# ESP_Robo_Board.net
KiCad netlist of a schematic drawn in EAGLE
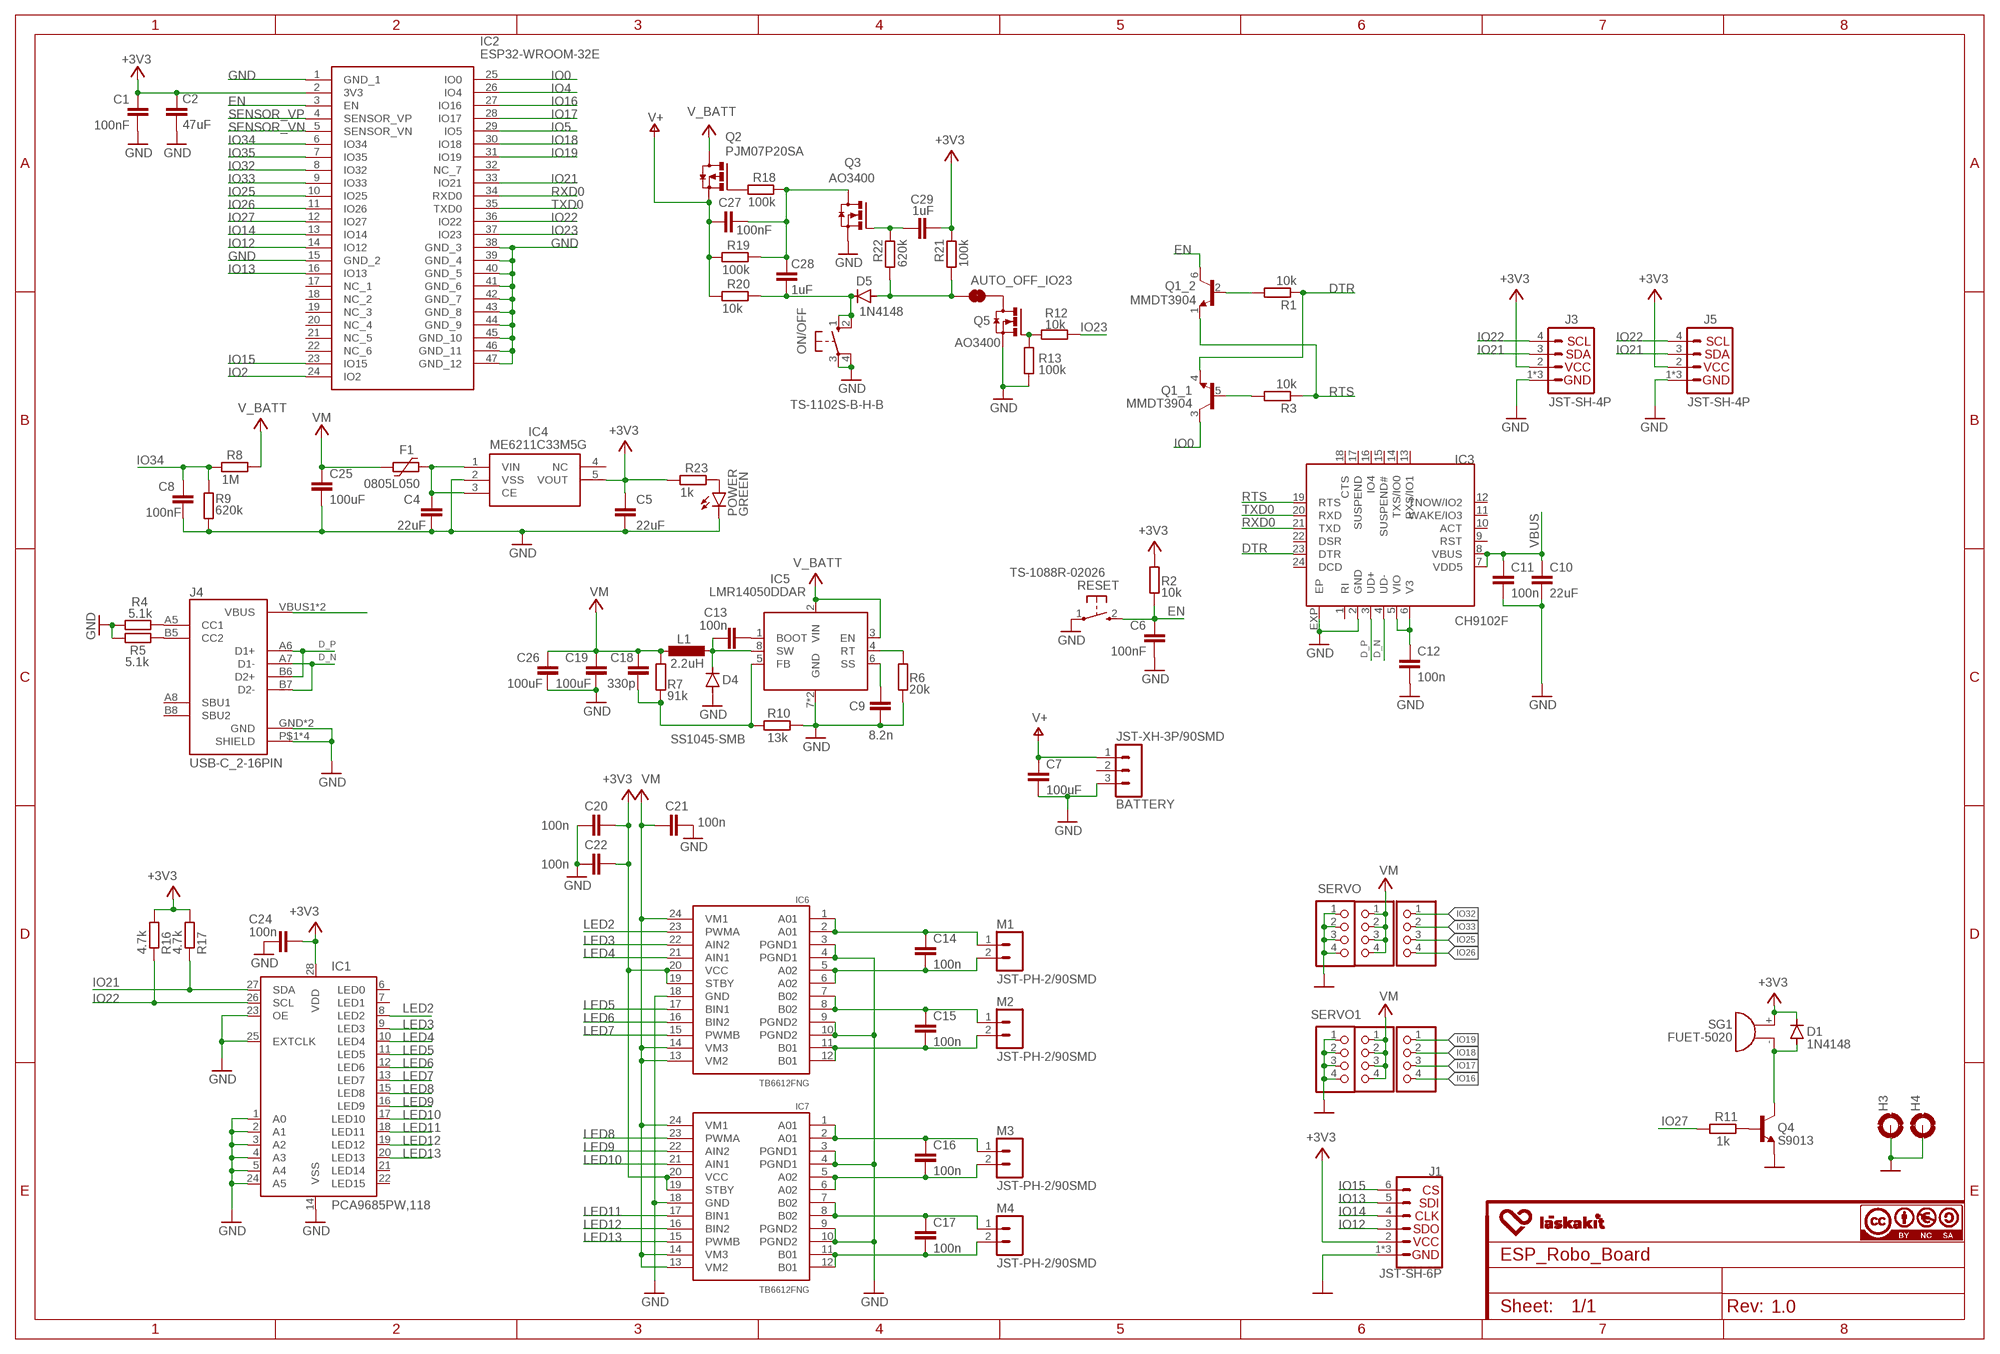
[diagram p0: schematic, sheet 1]

(export (version "E")
  (design (tool "Eeschema 10.0.6"))
  (components
    (comp (ref "1")
      (value "PINHD_1X4_RED")
      (footprint "eagle-import:1X04")
      (libsource (lib "eagle-import") (part "PINHD-1X4"))
    )
    (comp (ref "2")
      (value "PINHD_1X4_BLACK")
      (footprint "eagle-import:1X04")
      (libsource (lib "eagle-import") (part "PINHD-1X4"))
    )
    (comp (ref "5")
      (value "PINHD_1X4_RED")
      (footprint "eagle-import:1X04")
      (libsource (lib "eagle-import") (part "PINHD-1X4"))
    )
    (comp (ref "6")
      (value "PINHD_1X4_BLACK")
      (footprint "eagle-import:1X04")
      (libsource (lib "eagle-import") (part "PINHD-1X4"))
    )
    (comp (ref "AUTO_OFF_IO23")
      (value "nv")
      (footprint "eagle-import:SMT-JUMPER_2_NC_TRACE_SILK")
      (libsource (lib "eagle-import") (part "JUMPER-SMT_2_NC_TRACE_SILK"))
    )
    (comp (ref "BATTERY")
      (value "JST-XH-3P/90SMD")
      (footprint "eagle-import:S3B-XH-SM4")
      (libsource (lib "eagle-import") (part "JST-XH-3/90SMD"))
    )
    (comp (ref "C1")
      (value "100nF")
      (footprint "eagle-import:C0603")
      (libsource (lib "eagle-import") (part "C-EUC0603"))
    )
    (comp (ref "C2")
      (value "47uF")
      (footprint "eagle-import:C0805")
      (libsource (lib "eagle-import") (part "C-EUC0805"))
    )
    (comp (ref "C4")
      (value "22uF")
      (footprint "eagle-import:C0603")
      (libsource (lib "eagle-import") (part "C-EUC0603"))
    )
    (comp (ref "C5")
      (value "22uF")
      (footprint "eagle-import:C0603")
      (fields (field (name "LCSC_PART") "C19666"))
      (libsource (lib "eagle-import") (part "C-EUC0603"))
    )
    (comp (ref "C6")
      (value "100nF")
      (footprint "eagle-import:C0402")
      (libsource (lib "eagle-import") (part "CAPACITOR_0402"))
    )
    (comp (ref "C7")
      (value "100uF")
      (footprint "eagle-import:C1206")
      (libsource (lib "eagle-import") (part "C-EUC1206"))
    )
    (comp (ref "C8")
      (value "100nF")
      (footprint "eagle-import:C0402")
      (libsource (lib "eagle-import") (part "CAPACITOR_0402"))
    )
    (comp (ref "C9")
      (value "8.2n")
      (footprint "eagle-import:C0603")
      (libsource (lib "eagle-import") (part "C-EUC0603"))
    )
    (comp (ref "C10")
      (value "22uF")
      (footprint "eagle-import:C0603")
      (libsource (lib "eagle-import") (part "C-EUC0603"))
    )
    (comp (ref "C11")
      (value "100n")
      (footprint "eagle-import:C0402")
      (libsource (lib "eagle-import") (part "CAPACITOR_0402"))
    )
    (comp (ref "C12")
      (value "100n")
      (footprint "eagle-import:C0402")
      (libsource (lib "eagle-import") (part "CAPACITOR_0402"))
    )
    (comp (ref "C13")
      (value "100n")
      (footprint "eagle-import:C0603")
      (libsource (lib "eagle-import") (part "C-EUC0603"))
    )
    (comp (ref "C14")
      (value "100n")
      (footprint "eagle-import:C0603")
      (libsource (lib "eagle-import") (part "C-EUC0603"))
    )
    (comp (ref "C15")
      (value "100n")
      (footprint "eagle-import:C0603")
      (libsource (lib "eagle-import") (part "C-EUC0603"))
    )
    (comp (ref "C16")
      (value "100n")
      (footprint "eagle-import:C0603")
      (libsource (lib "eagle-import") (part "C-EUC0603"))
    )
    (comp (ref "C17")
      (value "100n")
      (footprint "eagle-import:C0603")
      (libsource (lib "eagle-import") (part "C-EUC0603"))
    )
    (comp (ref "C18")
      (value "330p")
      (footprint "eagle-import:C0402")
      (libsource (lib "eagle-import") (part "CAPACITOR_0402"))
    )
    (comp (ref "C19")
      (value "100uF")
      (footprint "eagle-import:C1206")
      (libsource (lib "eagle-import") (part "C-EUC1206"))
    )
    (comp (ref "C20")
      (value "100n")
      (footprint "eagle-import:C0603")
      (libsource (lib "eagle-import") (part "C-EUC0603"))
    )
    (comp (ref "C21")
      (value "100n")
      (footprint "eagle-import:C0603")
      (libsource (lib "eagle-import") (part "C-EUC0603"))
    )
    (comp (ref "C22")
      (value "100n")
      (footprint "eagle-import:C0603")
      (libsource (lib "eagle-import") (part "C-EUC0603"))
    )
    (comp (ref "C24")
      (value "100n")
      (footprint "eagle-import:C0603")
      (libsource (lib "eagle-import") (part "C-EUC0603"))
    )
    (comp (ref "C25")
      (value "100uF")
      (footprint "eagle-import:C1206")
      (libsource (lib "eagle-import") (part "C-EUC1206"))
    )
    (comp (ref "C26")
      (value "100uF")
      (footprint "eagle-import:C1206")
      (libsource (lib "eagle-import") (part "C-EUC1206"))
    )
    (comp (ref "C27")
      (value "100nF")
      (footprint "eagle-import:C0402")
      (libsource (lib "eagle-import") (part "CAPACITOR_0402"))
    )
    (comp (ref "C28")
      (value "1uF")
      (footprint "eagle-import:C0603")
      (libsource (lib "eagle-import") (part "C-EUC0603"))
    )
    (comp (ref "C29")
      (value "1uF")
      (footprint "eagle-import:C0603")
      (libsource (lib "eagle-import") (part "C-EUC0603"))
    )
    (comp (ref "D1")
      (value "1N4148")
      (footprint "eagle-import:SOD323-R")
      (fields (field (name "LCSC_PART") "C94001"))
      (libsource (lib "eagle-import") (part "DIODE-SOD323-R"))
    )
    (comp (ref "D4")
      (value "SS1045-SMB")
      (footprint "eagle-import:SMB")
      (fields (field (name "LCSC_PART") "C2903947"))
      (libsource (lib "eagle-import") (part "DIODE-SMB"))
    )
    (comp (ref "D5")
      (value "1N4148")
      (footprint "eagle-import:SOD323-R")
      (libsource (lib "eagle-import") (part "DIODE-SOD323-R"))
    )
    (comp (ref "F1")
      (value "0805L050")
      (footprint "eagle-import:0805L")
      (fields (field (name "MF") "Littelfuse") (field (name "LCSC_PART") "C66452"))
      (libsource (lib "eagle-import") (part "?0805L050"))
    )
    (comp (ref "H3")
      (value "MOUNT-PAD-ROUND2.5")
      (footprint "eagle-import:2,5-PAD")
      (libsource (lib "eagle-import") (part "MOUNT-PAD-ROUND2.5"))
    )
    (comp (ref "H4")
      (value "MOUNT-PAD-ROUND2.5")
      (footprint "eagle-import:2,5-PAD")
      (libsource (lib "eagle-import") (part "MOUNT-PAD-ROUND2.5"))
    )
    (comp (ref "IC1")
      (value "PCA9685PW,118")
      (footprint "eagle-import:TSSOP28")
      (fields (field (name "LCSC_PART") "C2678753"))
      (libsource (lib "eagle-import") (part "PCA9685PW,118"))
    )
    (comp (ref "IC2")
      (value "ESP32-WROOM-32E")
      (footprint "eagle-import:ESP32WROOM32E")
      (libsource (lib "eagle-import") (part "ESP32-WROOM-32E"))
    )
    (comp (ref "IC3")
      (value "CH9102F")
      (footprint "eagle-import:QFN24-4X4")
      (libsource (lib "eagle-import") (part "USB_UART_CONVERTOR_CH9102"))
    )
    (comp (ref "IC4")
      (value "ME6211C33M5G")
      (footprint "eagle-import:SOT23-5")
      (libsource (lib "eagle-import") (part "LDO_ME6211C33M5G"))
    )
    (comp (ref "IC5")
      (value "LMR14050DDAR")
      (footprint "eagle-import:SO08-EPAD")
      (fields (field (name "LCSC_PART") "C155484"))
      (libsource (lib "eagle-import") (part "LMR14050DDAR"))
    )
    (comp (ref "IC6")
      (value "TB6612FNG")
      (footprint "eagle-import:SSOP24")
      (libsource (lib "eagle-import") (part "MOTOR_DRIVER_TB6612FNG"))
    )
    (comp (ref "IC7")
      (value "TB6612FNG")
      (footprint "eagle-import:SSOP24")
      (libsource (lib "eagle-import") (part "MOTOR_DRIVER_TB6612FNG"))
    )
    (comp (ref "J1")
      (value "JST-SH-6P")
      (footprint "eagle-import:1X06_1MM_RA_VERT")
      (fields (field (name "LCSC_PART") "C145963"))
      (libsource (lib "eagle-import") (part "USUP_SPI_CONNECTOR_VERT"))
    )
    (comp (ref "J3")
      (value "JST-SH-4P")
      (footprint "eagle-import:1X04_1MM_RA_VERT")
      (fields (field (name "LCSC_PART") "C371588"))
      (libsource (lib "eagle-import") (part "USUP_I2C_CONNECTOR_VERT"))
    )
    (comp (ref "J4")
      (value "USB-C_2-16PIN")
      (footprint "eagle-import:USBC_USB-C-16P-5")
      (fields (field (name "LCSC_PART") "C2837092"))
      (libsource (lib "eagle-import") (part "USB-C_2-16PIN"))
    )
    (comp (ref "J5")
      (value "JST-SH-4P")
      (footprint "eagle-import:1X04_1MM_RA_VERT")
      (fields (field (name "LCSC_PART") "C371588"))
      (libsource (lib "eagle-import") (part "USUP_I2C_CONNECTOR_VERT"))
    )
    (comp (ref "L1")
      (value "2.2uH")
      (footprint "eagle-import:L5.4X5.2")
      (fields (field (name "LCSC_PART") "C351096"))
      (libsource (lib "eagle-import") (part "INDUCTOR_5.4X5.2"))
    )
    (comp (ref "M1")
      (value "JST-PH-2/90SMD")
      (footprint "eagle-import:S2B-PH-SM4")
      (fields (field (name "LCSC_PART") "C47647"))
      (libsource (lib "eagle-import") (part "JST-PH-2/90SMD"))
    )
    (comp (ref "M2")
      (value "JST-PH-2/90SMD")
      (footprint "eagle-import:S2B-PH-SM4")
      (fields (field (name "LCSC_PART") "C47647"))
      (libsource (lib "eagle-import") (part "JST-PH-2/90SMD"))
    )
    (comp (ref "M3")
      (value "JST-PH-2/90SMD")
      (footprint "eagle-import:S2B-PH-SM4")
      (fields (field (name "LCSC_PART") "C47647"))
      (libsource (lib "eagle-import") (part "JST-PH-2/90SMD"))
    )
    (comp (ref "M4")
      (value "JST-PH-2/90SMD")
      (footprint "eagle-import:S2B-PH-SM4")
      (fields (field (name "LCSC_PART") "C47647"))
      (libsource (lib "eagle-import") (part "JST-PH-2/90SMD"))
    )
    (comp (ref "ON/OFF")
      (value "TS-1102S-B-H-B")
      (footprint "eagle-import:B3F-SMD")
      (libsource (lib "eagle-import") (part "10-XX-SMD"))
    )
    (comp (ref "POWER")
      (value "GREEN")
      (footprint "eagle-import:CHIPLED_0402")
      (libsource (lib "eagle-import") (part "LEDCHIPLED_0402"))
    )
    (comp (ref "Q1")
      (value "MMDT3904")
      (footprint "eagle-import:SC70-6")
      (fields (field (name "LCSC_PART") "C268586"))
      (libsource (lib "eagle-import") (part "TRANS_NPN_DUAL-MBT3904DW1T1"))
    )
    (comp (ref "Q2")
      (value "PJM07P20SA")
      (footprint "eagle-import:SOT23")
      (fields (field (name "LCSC_PART") "C2856842"))
      (libsource (lib "eagle-import") (part "MOSFET_P-SOT-23"))
    )
    (comp (ref "Q3")
      (value "AO3400")
      (footprint "eagle-import:SOT23")
      (fields (field (name "LCSC_PART") "C693097"))
      (libsource (lib "eagle-import") (part "MOSFET_N-SOT-23"))
    )
    (comp (ref "Q4")
      (value "S9013")
      (footprint "eagle-import:SOT23-BEC")
      (fields (field (name "LCSC_PART") "C52801"))
      (libsource (lib "eagle-import") (part "-NPN-SOT23-BECBC817-16"))
    )
    (comp (ref "Q5")
      (value "AO3400")
      (footprint "eagle-import:SOT23")
      (fields (field (name "LCSC_PART") "C693097"))
      (libsource (lib "eagle-import") (part "MOSFET_N-SOT-23"))
    )
    (comp (ref "R1")
      (value "10k")
      (footprint "eagle-import:R0402")
      (libsource (lib "eagle-import") (part "R-EU_R0402"))
    )
    (comp (ref "R2")
      (value "10k")
      (footprint "eagle-import:R0402")
      (libsource (lib "eagle-import") (part "R-EU_R0402"))
    )
    (comp (ref "R3")
      (value "10k")
      (footprint "eagle-import:R0402")
      (libsource (lib "eagle-import") (part "R-EU_R0402"))
    )
    (comp (ref "R4")
      (value "5.1k")
      (footprint "eagle-import:R0402")
      (libsource (lib "eagle-import") (part "R-EU_R0402"))
    )
    (comp (ref "R5")
      (value "5.1k")
      (footprint "eagle-import:R0402")
      (libsource (lib "eagle-import") (part "R-EU_R0402"))
    )
    (comp (ref "R6")
      (value "20k")
      (footprint "eagle-import:R0402")
      (libsource (lib "eagle-import") (part "R-EU_R0402"))
    )
    (comp (ref "R7")
      (value "91k")
      (footprint "eagle-import:R0402")
      (libsource (lib "eagle-import") (part "R-EU_R0402"))
    )
    (comp (ref "R8")
      (value "1M")
      (footprint "eagle-import:R0402")
      (libsource (lib "eagle-import") (part "R-EU_R0402"))
    )
    (comp (ref "R9")
      (value "620k")
      (footprint "eagle-import:R0402")
      (libsource (lib "eagle-import") (part "R-EU_R0402"))
    )
    (comp (ref "R10")
      (value "13k")
      (footprint "eagle-import:R0402")
      (libsource (lib "eagle-import") (part "R-EU_R0402"))
    )
    (comp (ref "R11")
      (value "1k")
      (footprint "eagle-import:R0402")
      (fields (field (name "LCSC_PART") "C22548"))
      (libsource (lib "eagle-import") (part "R-EU_R0402"))
    )
    (comp (ref "R12")
      (value "10k")
      (footprint "eagle-import:R0402")
      (libsource (lib "eagle-import") (part "R-EU_R0402"))
    )
    (comp (ref "R13")
      (value "100k")
      (footprint "eagle-import:R0402")
      (libsource (lib "eagle-import") (part "R-EU_R0402"))
    )
    (comp (ref "R16")
      (value "4.7k")
      (footprint "eagle-import:R0402")
      (libsource (lib "eagle-import") (part "R-EU_R0402"))
    )
    (comp (ref "R17")
      (value "4.7k")
      (footprint "eagle-import:R0402")
      (libsource (lib "eagle-import") (part "R-EU_R0402"))
    )
    (comp (ref "R18")
      (value "100k")
      (footprint "eagle-import:R0402")
      (libsource (lib "eagle-import") (part "R-EU_R0402"))
    )
    (comp (ref "R19")
      (value "100k")
      (footprint "eagle-import:R0402")
      (libsource (lib "eagle-import") (part "R-EU_R0402"))
    )
    (comp (ref "R20")
      (value "10k")
      (footprint "eagle-import:R0402")
      (libsource (lib "eagle-import") (part "R-EU_R0402"))
    )
    (comp (ref "R21")
      (value "100k")
      (footprint "eagle-import:R0402")
      (libsource (lib "eagle-import") (part "R-EU_R0402"))
    )
    (comp (ref "R22")
      (value "620k")
      (footprint "eagle-import:R0402")
      (libsource (lib "eagle-import") (part "R-EU_R0402"))
    )
    (comp (ref "R23")
      (value "1k")
      (footprint "eagle-import:R0402")
      (libsource (lib "eagle-import") (part "R-EU_R0402"))
    )
    (comp (ref "RESET")
      (value "TS-1088R-02026")
      (footprint "eagle-import:TS1088R02026")
      (fields (field (name "LCSC_PART") "C455280"))
      (libsource (lib "eagle-import") (part "MOMENTARY_SWITCH_TS-1088R-02026"))
    )
    (comp (ref "SERVO")
      (value "PINHD_1X4_YELLOW")
      (footprint "eagle-import:1X04")
      (libsource (lib "eagle-import") (part "PINHD-1X4"))
    )
    (comp (ref "SERVO1")
      (value "PINHD_1X4_YELLOW")
      (footprint "eagle-import:1X04")
      (libsource (lib "eagle-import") (part "PINHD-1X4"))
    )
    (comp (ref "SG1")
      (value "FUET-5020")
      (footprint "eagle-import:FUET-5020")
      (fields (field (name "LCSC_PART") "C391029"))
      (libsource (lib "eagle-import") (part "PASSIVE_BUZZER_3V_FUET-5020"))
    )
  )
  (nets
    (net (code "1") (name "+3V3") (class "Default")
      (node (ref "C1") (pin "1") (pinfunction "1_1") (pintype "passive"))
      (node (ref "C2") (pin "1") (pinfunction "1_1") (pintype "passive"))
      (node (ref "C20") (pin "2") (pinfunction "2_2") (pintype "passive"))
      (node (ref "C22") (pin "2") (pinfunction "2_2") (pintype "passive"))
      (node (ref "C24") (pin "2") (pinfunction "2_2") (pintype "passive"))
      (node (ref "C29") (pin "1") (pinfunction "1_1") (pintype "passive"))
      (node (ref "C5") (pin "1") (pinfunction "1_1") (pintype "passive"))
      (node (ref "D1") (pin "C") (pinfunction "C_C") (pintype "passive"))
      (node (ref "IC1") (pin "28") (pinfunction "VDD_28") (pintype "bidirectional"))
      (node (ref "IC2") (pin "2") (pinfunction "3V3_2") (pintype "bidirectional"))
      (node (ref "IC4") (pin "5") (pinfunction "VOUT_5") (pintype "bidirectional"))
      (node (ref "IC6") (pin "19") (pinfunction "STBY_19") (pintype "bidirectional"))
      (node (ref "IC6") (pin "20") (pinfunction "VCC_20") (pintype "bidirectional"))
      (node (ref "IC7") (pin "19") (pinfunction "STBY_19") (pintype "bidirectional"))
      (node (ref "IC7") (pin "20") (pinfunction "VCC_20") (pintype "bidirectional"))
      (node (ref "J1") (pin "2") (pinfunction "VCC_2") (pintype "power_in"))
      (node (ref "J3") (pin "2") (pinfunction "VCC_2") (pintype "power_in"))
      (node (ref "J5") (pin "2") (pinfunction "VCC_2") (pintype "power_in"))
      (node (ref "R16") (pin "2") (pinfunction "2_2") (pintype "passive"))
      (node (ref "R17") (pin "2") (pinfunction "2_2") (pintype "passive"))
      (node (ref "R2") (pin "1") (pinfunction "1_1") (pintype "passive"))
      (node (ref "R21") (pin "2") (pinfunction "2_2") (pintype "passive"))
      (node (ref "R23") (pin "1") (pinfunction "1_1") (pintype "passive"))
      (node (ref "SG1") (pin "+") (pinfunction "+_+") (pintype "passive"))
    )
    (net (code "2") (name "/DTR") (class "Default")
      (node (ref "IC3") (pin "23") (pinfunction "DTR_23") (pintype "bidirectional"))
      (node (ref "Q1") (pin "4") (pinfunction "E_4") (pintype "passive"))
      (node (ref "R1") (pin "1") (pinfunction "1_1") (pintype "passive"))
    )
    (net (code "3") (name "/D_N") (class "Default")
      (node (ref "IC3") (pin "4") (pinfunction "UD-_4") (pintype "bidirectional"))
      (node (ref "J4") (pin "A7") (pinfunction "D1-_A7") (pintype "passive"))
      (node (ref "J4") (pin "B7") (pinfunction "D2-_B7") (pintype "passive"))
    )
    (net (code "4") (name "/D_P") (class "Default")
      (node (ref "IC3") (pin "3") (pinfunction "UD+_3") (pintype "bidirectional"))
      (node (ref "J4") (pin "A6") (pinfunction "D1+_A6") (pintype "passive"))
      (node (ref "J4") (pin "B6") (pinfunction "D2+_B6") (pintype "passive"))
    )
    (net (code "5") (name "/EN") (class "Default")
      (node (ref "C6") (pin "1") (pinfunction "1_1") (pintype "passive"))
      (node (ref "IC2") (pin "3") (pinfunction "EN_3") (pintype "bidirectional"))
      (node (ref "Q1") (pin "6") (pinfunction "C_6") (pintype "passive"))
      (node (ref "R2") (pin "2") (pinfunction "2_2") (pintype "passive"))
      (node (ref "RESET") (pin "2") (pinfunction "3_2") (pintype "passive"))
    )
    (net (code "6") (name "/IO0") (class "Default")
      (node (ref "IC2") (pin "25") (pinfunction "IO0_25") (pintype "bidirectional"))
      (node (ref "Q1") (pin "3") (pinfunction "C_3") (pintype "passive"))
    )
    (net (code "7") (name "/IO2") (class "Default")
      (node (ref "IC2") (pin "24") (pinfunction "IO2_24") (pintype "bidirectional"))
    )
    (net (code "8") (name "/IO4") (class "Default")
      (node (ref "IC2") (pin "26") (pinfunction "IO4_26") (pintype "bidirectional"))
    )
    (net (code "9") (name "/IO5") (class "Default")
      (node (ref "IC2") (pin "29") (pinfunction "IO5_29") (pintype "bidirectional"))
    )
    (net (code "10") (name "/IO12") (class "Default")
      (node (ref "IC2") (pin "14") (pinfunction "IO12_14") (pintype "bidirectional"))
      (node (ref "J1") (pin "3") (pinfunction "SDO_3") (pintype "passive"))
    )
    (net (code "11") (name "/IO13") (class "Default")
      (node (ref "IC2") (pin "16") (pinfunction "IO13_16") (pintype "bidirectional"))
      (node (ref "J1") (pin "5") (pinfunction "SDI_5") (pintype "passive"))
    )
    (net (code "12") (name "/IO14") (class "Default")
      (node (ref "IC2") (pin "13") (pinfunction "IO14_13") (pintype "bidirectional"))
      (node (ref "J1") (pin "4") (pinfunction "CLK_4") (pintype "passive"))
    )
    (net (code "13") (name "/IO15") (class "Default")
      (node (ref "IC2") (pin "23") (pinfunction "IO15_23") (pintype "bidirectional"))
      (node (ref "J1") (pin "6") (pinfunction "CS_6") (pintype "passive"))
    )
    (net (code "14") (name "/IO21") (class "Default")
      (node (ref "IC1") (pin "27") (pinfunction "SDA_27") (pintype "bidirectional"))
      (node (ref "IC2") (pin "33") (pinfunction "IO21_33") (pintype "bidirectional"))
      (node (ref "J3") (pin "3") (pinfunction "SDA_3") (pintype "passive"))
      (node (ref "J5") (pin "3") (pinfunction "SDA_3") (pintype "passive"))
      (node (ref "R17") (pin "1") (pinfunction "1_1") (pintype "passive"))
    )
    (net (code "15") (name "/IO22") (class "Default")
      (node (ref "IC1") (pin "26") (pinfunction "SCL_26") (pintype "bidirectional"))
      (node (ref "IC2") (pin "36") (pinfunction "IO22_36") (pintype "bidirectional"))
      (node (ref "J3") (pin "4") (pinfunction "SCL_4") (pintype "passive"))
      (node (ref "J5") (pin "4") (pinfunction "SCL_4") (pintype "passive"))
      (node (ref "R16") (pin "1") (pinfunction "1_1") (pintype "passive"))
    )
    (net (code "16") (name "/IO23") (class "Default")
      (node (ref "IC2") (pin "37") (pinfunction "IO23_37") (pintype "bidirectional"))
      (node (ref "R12") (pin "2") (pinfunction "2_2") (pintype "passive"))
    )
    (net (code "17") (name "/IO27") (class "Default")
      (node (ref "IC2") (pin "12") (pinfunction "IO27_12") (pintype "bidirectional"))
      (node (ref "R11") (pin "1") (pinfunction "1_1") (pintype "passive"))
    )
    (net (code "18") (name "/IO34") (class "Default")
      (node (ref "C8") (pin "1") (pinfunction "1_1") (pintype "passive"))
      (node (ref "IC2") (pin "6") (pinfunction "IO34_6") (pintype "bidirectional"))
      (node (ref "R8") (pin "1") (pinfunction "1_1") (pintype "passive"))
      (node (ref "R9") (pin "2") (pinfunction "2_2") (pintype "passive"))
    )
    (net (code "19") (name "/IO35") (class "Default")
      (node (ref "IC2") (pin "7") (pinfunction "IO35_7") (pintype "bidirectional"))
    )
    (net (code "20") (name "/LED2") (class "Default")
      (node (ref "IC1") (pin "8") (pinfunction "LED2_8") (pintype "bidirectional"))
      (node (ref "IC6") (pin "23") (pinfunction "PWMA_23") (pintype "bidirectional"))
    )
    (net (code "21") (name "/LED3") (class "Default")
      (node (ref "IC1") (pin "9") (pinfunction "LED3_9") (pintype "bidirectional"))
      (node (ref "IC6") (pin "22") (pinfunction "AIN2_22") (pintype "bidirectional"))
    )
    (net (code "22") (name "/LED4") (class "Default")
      (node (ref "IC1") (pin "10") (pinfunction "LED4_10") (pintype "bidirectional"))
      (node (ref "IC6") (pin "21") (pinfunction "AIN1_21") (pintype "bidirectional"))
    )
    (net (code "23") (name "/LED5") (class "Default")
      (node (ref "IC1") (pin "11") (pinfunction "LED5_11") (pintype "bidirectional"))
      (node (ref "IC6") (pin "17") (pinfunction "BIN1_17") (pintype "bidirectional"))
    )
    (net (code "24") (name "/LED6") (class "Default")
      (node (ref "IC1") (pin "12") (pinfunction "LED6_12") (pintype "bidirectional"))
      (node (ref "IC6") (pin "16") (pinfunction "BIN2_16") (pintype "bidirectional"))
    )
    (net (code "25") (name "/LED7") (class "Default")
      (node (ref "IC1") (pin "13") (pinfunction "LED7_13") (pintype "bidirectional"))
      (node (ref "IC6") (pin "15") (pinfunction "PWMB_15") (pintype "bidirectional"))
    )
    (net (code "26") (name "/LED8") (class "Default")
      (node (ref "IC1") (pin "15") (pinfunction "LED8_15") (pintype "bidirectional"))
      (node (ref "IC7") (pin "23") (pinfunction "PWMA_23") (pintype "bidirectional"))
    )
    (net (code "27") (name "/LED9") (class "Default")
      (node (ref "IC1") (pin "16") (pinfunction "LED9_16") (pintype "bidirectional"))
      (node (ref "IC7") (pin "22") (pinfunction "AIN2_22") (pintype "bidirectional"))
    )
    (net (code "28") (name "/LED10") (class "Default")
      (node (ref "IC1") (pin "17") (pinfunction "LED10_17") (pintype "bidirectional"))
      (node (ref "IC7") (pin "21") (pinfunction "AIN1_21") (pintype "bidirectional"))
    )
    (net (code "29") (name "/LED11") (class "Default")
      (node (ref "IC1") (pin "18") (pinfunction "LED11_18") (pintype "bidirectional"))
      (node (ref "IC7") (pin "17") (pinfunction "BIN1_17") (pintype "bidirectional"))
    )
    (net (code "30") (name "/LED12") (class "Default")
      (node (ref "IC1") (pin "19") (pinfunction "LED12_19") (pintype "bidirectional"))
      (node (ref "IC7") (pin "16") (pinfunction "BIN2_16") (pintype "bidirectional"))
    )
    (net (code "31") (name "/LED13") (class "Default")
      (node (ref "IC1") (pin "20") (pinfunction "LED13_20") (pintype "bidirectional"))
      (node (ref "IC7") (pin "15") (pinfunction "PWMB_15") (pintype "bidirectional"))
    )
    (net (code "32") (name "/RTS") (class "Default")
      (node (ref "IC3") (pin "19") (pinfunction "RTS_19") (pintype "bidirectional"))
      (node (ref "Q1") (pin "1") (pinfunction "E_1") (pintype "passive"))
      (node (ref "R3") (pin "1") (pinfunction "1_1") (pintype "passive"))
    )
    (net (code "33") (name "/RXD0") (class "Default")
      (node (ref "IC2") (pin "34") (pinfunction "RXD0_34") (pintype "bidirectional"))
      (node (ref "IC3") (pin "21") (pinfunction "TXD_21") (pintype "bidirectional"))
    )
    (net (code "34") (name "/SENSOR_VN") (class "Default")
      (node (ref "IC2") (pin "5") (pinfunction "SENSOR_VN_5") (pintype "bidirectional"))
    )
    (net (code "35") (name "/SENSOR_VP") (class "Default")
      (node (ref "IC2") (pin "4") (pinfunction "SENSOR_VP_4") (pintype "bidirectional"))
    )
    (net (code "36") (name "/TXD0") (class "Default")
      (node (ref "IC2") (pin "35") (pinfunction "TXD0_35") (pintype "bidirectional"))
      (node (ref "IC3") (pin "20") (pinfunction "RXD_20") (pintype "bidirectional"))
    )
    (net (code "37") (name "/VBUS") (class "Default")
      (node (ref "C10") (pin "1") (pinfunction "1_1") (pintype "passive"))
      (node (ref "C11") (pin "1") (pinfunction "1_1") (pintype "passive"))
      (node (ref "IC3") (pin "7") (pinfunction "VDD5_7") (pintype "bidirectional"))
      (node (ref "IC3") (pin "8") (pinfunction "VBUS_8") (pintype "bidirectional"))
      (node (ref "J4") (pin "VBUS1") (pinfunction "VBUS_VBUS1") (pintype "passive"))
      (node (ref "J4") (pin "VBUS2") (pinfunction "VBUS_VBUS2") (pintype "passive"))
    )
    (net (code "38") (name "GND") (class "Default")
      (node (ref "2") (pin "1") (pinfunction "1_1") (pintype "passive"))
      (node (ref "2") (pin "2") (pinfunction "2_2") (pintype "passive"))
      (node (ref "2") (pin "3") (pinfunction "3_3") (pintype "passive"))
      (node (ref "2") (pin "4") (pinfunction "4_4") (pintype "passive"))
      (node (ref "6") (pin "1") (pinfunction "1_1") (pintype "passive"))
      (node (ref "6") (pin "2") (pinfunction "2_2") (pintype "passive"))
      (node (ref "6") (pin "3") (pinfunction "3_3") (pintype "passive"))
      (node (ref "6") (pin "4") (pinfunction "4_4") (pintype "passive"))
      (node (ref "BATTERY") (pin "3") (pinfunction "1_3") (pintype "passive"))
      (node (ref "C1") (pin "2") (pinfunction "2_2") (pintype "passive"))
      (node (ref "C10") (pin "2") (pinfunction "2_2") (pintype "passive"))
      (node (ref "C11") (pin "2") (pinfunction "2_2") (pintype "passive"))
      (node (ref "C12") (pin "2") (pinfunction "2_2") (pintype "passive"))
      (node (ref "C19") (pin "2") (pinfunction "2_2") (pintype "passive"))
      (node (ref "C2") (pin "2") (pinfunction "2_2") (pintype "passive"))
      (node (ref "C20") (pin "1") (pinfunction "1_1") (pintype "passive"))
      (node (ref "C21") (pin "2") (pinfunction "2_2") (pintype "passive"))
      (node (ref "C22") (pin "1") (pinfunction "1_1") (pintype "passive"))
      (node (ref "C24") (pin "1") (pinfunction "1_1") (pintype "passive"))
      (node (ref "C25") (pin "2") (pinfunction "2_2") (pintype "passive"))
      (node (ref "C26") (pin "2") (pinfunction "2_2") (pintype "passive"))
      (node (ref "C4") (pin "2") (pinfunction "2_2") (pintype "passive"))
      (node (ref "C5") (pin "2") (pinfunction "2_2") (pintype "passive"))
      (node (ref "C6") (pin "2") (pinfunction "2_2") (pintype "passive"))
      (node (ref "C7") (pin "2") (pinfunction "2_2") (pintype "passive"))
      (node (ref "C8") (pin "2") (pinfunction "2_2") (pintype "passive"))
      (node (ref "C9") (pin "2") (pinfunction "2_2") (pintype "passive"))
      (node (ref "D4") (pin "A") (pinfunction "A_A") (pintype "passive"))
      (node (ref "H3") (pin "1") (pinfunction "MOUNT_1") (pintype "passive"))
      (node (ref "H4") (pin "1") (pinfunction "MOUNT_1") (pintype "passive"))
      (node (ref "IC1") (pin "1") (pinfunction "A0_1") (pintype "bidirectional"))
      (node (ref "IC1") (pin "14") (pinfunction "VSS_14") (pintype "bidirectional"))
      (node (ref "IC1") (pin "2") (pinfunction "A1_2") (pintype "bidirectional"))
      (node (ref "IC1") (pin "23") (pinfunction "OE_23") (pintype "bidirectional"))
      (node (ref "IC1") (pin "24") (pinfunction "A5_24") (pintype "bidirectional"))
      (node (ref "IC1") (pin "25") (pinfunction "EXTCLK_25") (pintype "bidirectional"))
      (node (ref "IC1") (pin "3") (pinfunction "A2_3") (pintype "bidirectional"))
      (node (ref "IC1") (pin "4") (pinfunction "A3_4") (pintype "bidirectional"))
      (node (ref "IC1") (pin "5") (pinfunction "A4_5") (pintype "bidirectional"))
      (node (ref "IC2") (pin "1") (pinfunction "GND_1_1") (pintype "bidirectional"))
      (node (ref "IC2") (pin "15") (pinfunction "GND_2_15") (pintype "bidirectional"))
      (node (ref "IC2") (pin "38") (pinfunction "GND_3_38") (pintype "bidirectional"))
      (node (ref "IC2") (pin "39") (pinfunction "GND_4_39") (pintype "bidirectional"))
      (node (ref "IC2") (pin "40") (pinfunction "GND_5_40") (pintype "bidirectional"))
      (node (ref "IC2") (pin "41") (pinfunction "GND_6_41") (pintype "bidirectional"))
      (node (ref "IC2") (pin "42") (pinfunction "GND_7_42") (pintype "bidirectional"))
      (node (ref "IC2") (pin "43") (pinfunction "GND_8_43") (pintype "bidirectional"))
      (node (ref "IC2") (pin "44") (pinfunction "GND_9_44") (pintype "bidirectional"))
      (node (ref "IC2") (pin "45") (pinfunction "GND_10_45") (pintype "bidirectional"))
      (node (ref "IC2") (pin "46") (pinfunction "GND_11_46") (pintype "bidirectional"))
      (node (ref "IC2") (pin "47") (pinfunction "GND_12_47") (pintype "bidirectional"))
      (node (ref "IC3") (pin "2") (pinfunction "GND_2") (pintype "bidirectional"))
      (node (ref "IC3") (pin "EXP") (pinfunction "EP_EXP") (pintype "bidirectional"))
      (node (ref "IC4") (pin "2") (pinfunction "VSS_2") (pintype "bidirectional"))
      (node (ref "IC5") (pin "7") (pinfunction "GND_7") (pintype "bidirectional"))
      (node (ref "IC5") (pin "EPAD") (pinfunction "GND_EPAD") (pintype "bidirectional"))
      (node (ref "IC6") (pin "10") (pinfunction "PGND2_10") (pintype "bidirectional"))
      (node (ref "IC6") (pin "18") (pinfunction "GND_18") (pintype "bidirectional"))
      (node (ref "IC6") (pin "3") (pinfunction "PGND1_3") (pintype "bidirectional"))
      (node (ref "IC6") (pin "4") (pinfunction "PGND1_4") (pintype "bidirectional"))
      (node (ref "IC6") (pin "9") (pinfunction "PGND2_9") (pintype "bidirectional"))
      (node (ref "IC7") (pin "10") (pinfunction "PGND2_10") (pintype "bidirectional"))
      (node (ref "IC7") (pin "18") (pinfunction "GND_18") (pintype "bidirectional"))
      (node (ref "IC7") (pin "3") (pinfunction "PGND1_3") (pintype "bidirectional"))
      (node (ref "IC7") (pin "4") (pinfunction "PGND1_4") (pintype "bidirectional"))
      (node (ref "IC7") (pin "9") (pinfunction "PGND2_9") (pintype "bidirectional"))
      (node (ref "J1") (pin "1") (pinfunction "GND_1") (pintype "power_in"))
      (node (ref "J1") (pin "NC1") (pinfunction "GND_NC1") (pintype "power_in"))
      (node (ref "J1") (pin "NC2") (pinfunction "GND_NC2") (pintype "power_in"))
      (node (ref "J3") (pin "1") (pinfunction "GND_1") (pintype "power_in"))
      (node (ref "J3") (pin "NC1") (pinfunction "GND_NC1") (pintype "power_in"))
      (node (ref "J3") (pin "NC2") (pinfunction "GND_NC2") (pintype "power_in"))
      (node (ref "J4") (pin "GND") (pinfunction "GND_GND") (pintype "passive"))
      (node (ref "J4") (pin "GND2") (pinfunction "GND_GND2") (pintype "passive"))
      (node (ref "J4") (pin "P$1") (pinfunction "SHIELD_P$1") (pintype "passive"))
      (node (ref "J4") (pin "P$2") (pinfunction "SHIELD_P$2") (pintype "passive"))
      (node (ref "J4") (pin "P$3") (pinfunction "SHIELD_P$3") (pintype "passive"))
      (node (ref "J4") (pin "P$4") (pinfunction "SHIELD_P$4") (pintype "passive"))
      (node (ref "J5") (pin "1") (pinfunction "GND_1") (pintype "power_in"))
      (node (ref "J5") (pin "NC1") (pinfunction "GND_NC1") (pintype "power_in"))
      (node (ref "J5") (pin "NC2") (pinfunction "GND_NC2") (pintype "power_in"))
      (node (ref "ON/OFF") (pin "3") (pinfunction "P_3") (pintype "passive"))
      (node (ref "ON/OFF") (pin "4") (pinfunction "P1_4") (pintype "passive"))
      (node (ref "POWER") (pin "C") (pinfunction "C_C") (pintype "passive"))
      (node (ref "Q3") (pin "2") (pinfunction "S_2") (pintype "passive"))
      (node (ref "Q4") (pin "E") (pinfunction "E_E") (pintype "passive"))
      (node (ref "Q5") (pin "2") (pinfunction "S_2") (pintype "passive"))
      (node (ref "R10") (pin "2") (pinfunction "2_2") (pintype "passive"))
      (node (ref "R13") (pin "1") (pinfunction "1_1") (pintype "passive"))
      (node (ref "R4") (pin "1") (pinfunction "1_1") (pintype "passive"))
      (node (ref "R5") (pin "1") (pinfunction "1_1") (pintype "passive"))
      (node (ref "R6") (pin "2") (pinfunction "2_2") (pintype "passive"))
      (node (ref "R9") (pin "1") (pinfunction "1_1") (pintype "passive"))
      (node (ref "RESET") (pin "1") (pinfunction "1_1") (pintype "passive"))
    )
    (net (code "39") (name "IO16") (class "Default")
      (node (ref "IC2") (pin "27") (pinfunction "IO16_27") (pintype "bidirectional"))
      (node (ref "SERVO1") (pin "4") (pinfunction "4_4") (pintype "passive"))
    )
    (net (code "40") (name "IO17") (class "Default")
      (node (ref "IC2") (pin "28") (pinfunction "IO17_28") (pintype "bidirectional"))
      (node (ref "SERVO1") (pin "3") (pinfunction "3_3") (pintype "passive"))
    )
    (net (code "41") (name "IO18") (class "Default")
      (node (ref "IC2") (pin "30") (pinfunction "IO18_30") (pintype "bidirectional"))
      (node (ref "SERVO1") (pin "2") (pinfunction "2_2") (pintype "passive"))
    )
    (net (code "42") (name "IO19") (class "Default")
      (node (ref "IC2") (pin "31") (pinfunction "IO19_31") (pintype "bidirectional"))
      (node (ref "SERVO1") (pin "1") (pinfunction "1_1") (pintype "passive"))
    )
    (net (code "43") (name "IO25") (class "Default")
      (node (ref "IC2") (pin "10") (pinfunction "IO25_10") (pintype "bidirectional"))
      (node (ref "SERVO") (pin "3") (pinfunction "3_3") (pintype "passive"))
    )
    (net (code "44") (name "IO26") (class "Default")
      (node (ref "IC2") (pin "11") (pinfunction "IO26_11") (pintype "bidirectional"))
      (node (ref "SERVO") (pin "4") (pinfunction "4_4") (pintype "passive"))
    )
    (net (code "45") (name "IO32") (class "Default")
      (node (ref "IC2") (pin "8") (pinfunction "IO32_8") (pintype "bidirectional"))
      (node (ref "SERVO") (pin "1") (pinfunction "1_1") (pintype "passive"))
    )
    (net (code "46") (name "IO33") (class "Default")
      (node (ref "IC2") (pin "9") (pinfunction "IO33_9") (pintype "bidirectional"))
      (node (ref "SERVO") (pin "2") (pinfunction "2_2") (pintype "passive"))
    )
    (net (code "47") (name "Net-(AUTO_OFF_IO23-Pad1)") (class "Default")
      (node (ref "AUTO_OFF_IO23") (pin "1") (pinfunction "1_1") (pintype "passive"))
      (node (ref "D5") (pin "A") (pinfunction "A_A") (pintype "passive"))
      (node (ref "R21") (pin "1") (pinfunction "1_1") (pintype "passive"))
      (node (ref "R22") (pin "1") (pinfunction "1_1") (pintype "passive"))
    )
    (net (code "48") (name "Net-(C14-Pad1)") (class "Default")
      (node (ref "C14") (pin "1") (pinfunction "1_1") (pintype "passive"))
      (node (ref "IC6") (pin "1") (pinfunction "A01_1") (pintype "bidirectional"))
      (node (ref "IC6") (pin "2") (pinfunction "A01_2") (pintype "bidirectional"))
      (node (ref "M1") (pin "1") (pinfunction "1_1") (pintype "passive"))
    )
    (net (code "49") (name "Net-(C14-Pad2)") (class "Default")
      (node (ref "C14") (pin "2") (pinfunction "2_2") (pintype "passive"))
      (node (ref "IC6") (pin "5") (pinfunction "A02_5") (pintype "bidirectional"))
      (node (ref "IC6") (pin "6") (pinfunction "A02_6") (pintype "bidirectional"))
      (node (ref "M1") (pin "2") (pinfunction "2_2") (pintype "passive"))
    )
    (net (code "50") (name "Net-(C15-Pad1)") (class "Default")
      (node (ref "C15") (pin "1") (pinfunction "1_1") (pintype "passive"))
      (node (ref "IC6") (pin "7") (pinfunction "B02_7") (pintype "bidirectional"))
      (node (ref "IC6") (pin "8") (pinfunction "B02_8") (pintype "bidirectional"))
      (node (ref "M2") (pin "1") (pinfunction "1_1") (pintype "passive"))
    )
    (net (code "51") (name "Net-(C15-Pad2)") (class "Default")
      (node (ref "C15") (pin "2") (pinfunction "2_2") (pintype "passive"))
      (node (ref "IC6") (pin "11") (pinfunction "B01_11") (pintype "bidirectional"))
      (node (ref "IC6") (pin "12") (pinfunction "B01_12") (pintype "bidirectional"))
      (node (ref "M2") (pin "2") (pinfunction "2_2") (pintype "passive"))
    )
    (net (code "52") (name "Net-(C16-Pad1)") (class "Default")
      (node (ref "C16") (pin "1") (pinfunction "1_1") (pintype "passive"))
      (node (ref "IC7") (pin "1") (pinfunction "A01_1") (pintype "bidirectional"))
      (node (ref "IC7") (pin "2") (pinfunction "A01_2") (pintype "bidirectional"))
      (node (ref "M3") (pin "1") (pinfunction "1_1") (pintype "passive"))
    )
    (net (code "53") (name "Net-(C16-Pad2)") (class "Default")
      (node (ref "C16") (pin "2") (pinfunction "2_2") (pintype "passive"))
      (node (ref "IC7") (pin "5") (pinfunction "A02_5") (pintype "bidirectional"))
      (node (ref "IC7") (pin "6") (pinfunction "A02_6") (pintype "bidirectional"))
      (node (ref "M3") (pin "2") (pinfunction "2_2") (pintype "passive"))
    )
    (net (code "54") (name "Net-(C17-Pad1)") (class "Default")
      (node (ref "C17") (pin "1") (pinfunction "1_1") (pintype "passive"))
      (node (ref "IC7") (pin "7") (pinfunction "B02_7") (pintype "bidirectional"))
      (node (ref "IC7") (pin "8") (pinfunction "B02_8") (pintype "bidirectional"))
      (node (ref "M4") (pin "1") (pinfunction "1_1") (pintype "passive"))
    )
    (net (code "55") (name "Net-(C17-Pad2)") (class "Default")
      (node (ref "C17") (pin "2") (pinfunction "2_2") (pintype "passive"))
      (node (ref "IC7") (pin "11") (pinfunction "B01_11") (pintype "bidirectional"))
      (node (ref "IC7") (pin "12") (pinfunction "B01_12") (pintype "bidirectional"))
      (node (ref "M4") (pin "2") (pinfunction "2_2") (pintype "passive"))
    )
    (net (code "56") (name "Net-(D1-PadA)") (class "Default")
      (node (ref "D1") (pin "A") (pinfunction "A_A") (pintype "passive"))
      (node (ref "Q4") (pin "C") (pinfunction "C_C") (pintype "passive"))
      (node (ref "SG1") (pin "-") (pinfunction "-_-") (pintype "passive"))
    )
    (net (code "57") (name "Net-(IC3-V3)") (class "Default")
      (node (ref "C12") (pin "1") (pinfunction "1_1") (pintype "passive"))
      (node (ref "IC3") (pin "5") (pinfunction "VIO_5") (pintype "bidirectional"))
      (node (ref "IC3") (pin "6") (pinfunction "V3_6") (pintype "bidirectional"))
    )
    (net (code "58") (name "Net-(IC4-CE)") (class "Default")
      (node (ref "C4") (pin "1") (pinfunction "1_1") (pintype "passive"))
      (node (ref "F1") (pin "1") (pinfunction "1_1") (pintype "passive"))
      (node (ref "IC4") (pin "1") (pinfunction "VIN_1") (pintype "bidirectional"))
      (node (ref "IC4") (pin "3") (pinfunction "CE_3") (pintype "bidirectional"))
    )
    (net (code "59") (name "Net-(IC5-BOOT)") (class "Default")
      (node (ref "C13") (pin "2") (pinfunction "2_2") (pintype "passive"))
      (node (ref "IC5") (pin "1") (pinfunction "BOOT_1") (pintype "bidirectional"))
    )
    (net (code "60") (name "Net-(IC5-FB)") (class "Default")
      (node (ref "C18") (pin "2") (pinfunction "2_2") (pintype "passive"))
      (node (ref "IC5") (pin "5") (pinfunction "FB_5") (pintype "bidirectional"))
      (node (ref "R10") (pin "1") (pinfunction "1_1") (pintype "passive"))
      (node (ref "R7") (pin "2") (pinfunction "2_2") (pintype "passive"))
    )
    (net (code "61") (name "Net-(IC5-RT)") (class "Default")
      (node (ref "IC5") (pin "4") (pinfunction "RT_4") (pintype "bidirectional"))
      (node (ref "R6") (pin "1") (pinfunction "1_1") (pintype "passive"))
    )
    (net (code "62") (name "Net-(IC5-SS)") (class "Default")
      (node (ref "C9") (pin "1") (pinfunction "1_1") (pintype "passive"))
      (node (ref "IC5") (pin "6") (pinfunction "SS_6") (pintype "bidirectional"))
    )
    (net (code "63") (name "Net-(IC5-SW)") (class "Default")
      (node (ref "C13") (pin "1") (pinfunction "1_1") (pintype "passive"))
      (node (ref "D4") (pin "C") (pinfunction "C_C") (pintype "passive"))
      (node (ref "IC5") (pin "8") (pinfunction "SW_8") (pintype "bidirectional"))
      (node (ref "L1") (pin "1") (pinfunction "1_1") (pintype "passive"))
    )
    (net (code "64") (name "Net-(J4-CC1)") (class "Default")
      (node (ref "J4") (pin "A5") (pinfunction "CC1_A5") (pintype "passive"))
      (node (ref "R4") (pin "2") (pinfunction "2_2") (pintype "passive"))
    )
    (net (code "65") (name "Net-(J4-CC2)") (class "Default")
      (node (ref "J4") (pin "B5") (pinfunction "CC2_B5") (pintype "passive"))
      (node (ref "R5") (pin "2") (pinfunction "2_2") (pintype "passive"))
    )
    (net (code "66") (name "Net-(ON/OFF-S)") (class "Default")
      (node (ref "C28") (pin "2") (pinfunction "2_2") (pintype "passive"))
      (node (ref "D5") (pin "C") (pinfunction "C_C") (pintype "passive"))
      (node (ref "ON/OFF") (pin "1") (pinfunction "S_1") (pintype "passive"))
      (node (ref "ON/OFF") (pin "2") (pinfunction "S1_2") (pintype "passive"))
      (node (ref "R20") (pin "2") (pinfunction "2_2") (pintype "passive"))
    )
    (net (code "67") (name "Net-(POWER-PadA)") (class "Default")
      (node (ref "POWER") (pin "A") (pinfunction "A_A") (pintype "passive"))
      (node (ref "R23") (pin "2") (pinfunction "2_2") (pintype "passive"))
    )
    (net (code "68") (name "Net-(Q1A-B)") (class "Default")
      (node (ref "Q1") (pin "5") (pinfunction "B_5") (pintype "passive"))
      (node (ref "R3") (pin "2") (pinfunction "2_2") (pintype "passive"))
    )
    (net (code "69") (name "Net-(Q1B-B)") (class "Default")
      (node (ref "Q1") (pin "2") (pinfunction "B_2") (pintype "passive"))
      (node (ref "R1") (pin "2") (pinfunction "2_2") (pintype "passive"))
    )
    (net (code "70") (name "Net-(Q2-G)") (class "Default")
      (node (ref "Q2") (pin "1") (pinfunction "G_1") (pintype "passive"))
      (node (ref "R18") (pin "1") (pinfunction "1_1") (pintype "passive"))
    )
    (net (code "71") (name "Net-(Q3-D)") (class "Default")
      (node (ref "C27") (pin "2") (pinfunction "2_2") (pintype "passive"))
      (node (ref "C28") (pin "1") (pinfunction "1_1") (pintype "passive"))
      (node (ref "Q3") (pin "3") (pinfunction "D_3") (pintype "passive"))
      (node (ref "R18") (pin "2") (pinfunction "2_2") (pintype "passive"))
      (node (ref "R19") (pin "2") (pinfunction "2_2") (pintype "passive"))
    )
    (net (code "72") (name "Net-(Q3-G)") (class "Default")
      (node (ref "C29") (pin "2") (pinfunction "2_2") (pintype "passive"))
      (node (ref "Q3") (pin "1") (pinfunction "G_1") (pintype "passive"))
      (node (ref "R22") (pin "2") (pinfunction "2_2") (pintype "passive"))
    )
    (net (code "73") (name "Net-(Q4-PadB)") (class "Default")
      (node (ref "Q4") (pin "B") (pinfunction "B_B") (pintype "passive"))
      (node (ref "R11") (pin "2") (pinfunction "2_2") (pintype "passive"))
    )
    (net (code "74") (name "Net-(Q5-D)") (class "Default")
      (node (ref "AUTO_OFF_IO23") (pin "2") (pinfunction "2_2") (pintype "passive"))
      (node (ref "Q5") (pin "3") (pinfunction "D_3") (pintype "passive"))
    )
    (net (code "75") (name "Net-(Q5-G)") (class "Default")
      (node (ref "Q5") (pin "1") (pinfunction "G_1") (pintype "passive"))
      (node (ref "R12") (pin "1") (pinfunction "1_1") (pintype "passive"))
      (node (ref "R13") (pin "2") (pinfunction "2_2") (pintype "passive"))
    )
    (net (code "76") (name "V+") (class "Default")
      (node (ref "BATTERY") (pin "1") (pinfunction "3_1") (pintype "passive"))
      (node (ref "C27") (pin "1") (pinfunction "1_1") (pintype "passive"))
      (node (ref "C7") (pin "1") (pinfunction "1_1") (pintype "passive"))
      (node (ref "Q2") (pin "2") (pinfunction "S_2") (pintype "passive"))
      (node (ref "R19") (pin "1") (pinfunction "1_1") (pintype "passive"))
      (node (ref "R20") (pin "1") (pinfunction "1_1") (pintype "passive"))
    )
    (net (code "77") (name "VM") (class "Default")
      (node (ref "1") (pin "1") (pinfunction "1_1") (pintype "passive"))
      (node (ref "1") (pin "2") (pinfunction "2_2") (pintype "passive"))
      (node (ref "1") (pin "3") (pinfunction "3_3") (pintype "passive"))
      (node (ref "1") (pin "4") (pinfunction "4_4") (pintype "passive"))
      (node (ref "5") (pin "1") (pinfunction "1_1") (pintype "passive"))
      (node (ref "5") (pin "2") (pinfunction "2_2") (pintype "passive"))
      (node (ref "5") (pin "3") (pinfunction "3_3") (pintype "passive"))
      (node (ref "5") (pin "4") (pinfunction "4_4") (pintype "passive"))
      (node (ref "C18") (pin "1") (pinfunction "1_1") (pintype "passive"))
      (node (ref "C19") (pin "1") (pinfunction "1_1") (pintype "passive"))
      (node (ref "C21") (pin "1") (pinfunction "1_1") (pintype "passive"))
      (node (ref "C25") (pin "1") (pinfunction "1_1") (pintype "passive"))
      (node (ref "C26") (pin "1") (pinfunction "1_1") (pintype "passive"))
      (node (ref "F1") (pin "2") (pinfunction "2_2") (pintype "passive"))
      (node (ref "IC6") (pin "13") (pinfunction "VM2_13") (pintype "bidirectional"))
      (node (ref "IC6") (pin "14") (pinfunction "VM3_14") (pintype "bidirectional"))
      (node (ref "IC6") (pin "24") (pinfunction "VM1_24") (pintype "bidirectional"))
      (node (ref "IC7") (pin "13") (pinfunction "VM2_13") (pintype "bidirectional"))
      (node (ref "IC7") (pin "14") (pinfunction "VM3_14") (pintype "bidirectional"))
      (node (ref "IC7") (pin "24") (pinfunction "VM1_24") (pintype "bidirectional"))
      (node (ref "L1") (pin "2") (pinfunction "2_2") (pintype "passive"))
      (node (ref "R7") (pin "1") (pinfunction "1_1") (pintype "passive"))
    )
    (net (code "78") (name "V_BATT") (class "Default")
      (node (ref "IC5") (pin "2") (pinfunction "VIN_2") (pintype "bidirectional"))
      (node (ref "IC5") (pin "3") (pinfunction "EN_3") (pintype "bidirectional"))
      (node (ref "Q2") (pin "3") (pinfunction "D_3") (pintype "passive"))
      (node (ref "R8") (pin "2") (pinfunction "2_2") (pintype "passive"))
    )
    (net (code "79") (name "unconnected-(BATTERY-Pad2)") (class "Default")
      (node (ref "BATTERY") (pin "2") (pinfunction "2_2") (pintype "passive"))
    )
    (net (code "80") (name "unconnected-(IC1-LED0-Pad6)") (class "Default")
      (node (ref "IC1") (pin "6") (pinfunction "LED0_6") (pintype "bidirectional"))
    )
    (net (code "81") (name "unconnected-(IC1-LED1-Pad7)") (class "Default")
      (node (ref "IC1") (pin "7") (pinfunction "LED1_7") (pintype "bidirectional"))
    )
    (net (code "82") (name "unconnected-(IC1-LED14-Pad21)") (class "Default")
      (node (ref "IC1") (pin "21") (pinfunction "LED14_21") (pintype "bidirectional"))
    )
    (net (code "83") (name "unconnected-(IC1-LED15-Pad22)") (class "Default")
      (node (ref "IC1") (pin "22") (pinfunction "LED15_22") (pintype "bidirectional"))
    )
    (net (code "84") (name "unconnected-(IC2-NC_1-Pad17)") (class "Default")
      (node (ref "IC2") (pin "17") (pinfunction "NC_1_17") (pintype "bidirectional"))
    )
    (net (code "85") (name "unconnected-(IC2-NC_2-Pad18)") (class "Default")
      (node (ref "IC2") (pin "18") (pinfunction "NC_2_18") (pintype "bidirectional"))
    )
    (net (code "86") (name "unconnected-(IC2-NC_3-Pad19)") (class "Default")
      (node (ref "IC2") (pin "19") (pinfunction "NC_3_19") (pintype "bidirectional"))
    )
    (net (code "87") (name "unconnected-(IC2-NC_4-Pad20)") (class "Default")
      (node (ref "IC2") (pin "20") (pinfunction "NC_4_20") (pintype "bidirectional"))
    )
    (net (code "88") (name "unconnected-(IC2-NC_5-Pad21)") (class "Default")
      (node (ref "IC2") (pin "21") (pinfunction "NC_5_21") (pintype "bidirectional"))
    )
    (net (code "89") (name "unconnected-(IC2-NC_6-Pad22)") (class "Default")
      (node (ref "IC2") (pin "22") (pinfunction "NC_6_22") (pintype "bidirectional"))
    )
    (net (code "90") (name "unconnected-(IC2-NC_7-Pad32)") (class "Default")
      (node (ref "IC2") (pin "32") (pinfunction "NC_7_32") (pintype "no_connect"))
    )
    (net (code "91") (name "unconnected-(IC3-ACT-Pad10)") (class "Default")
      (node (ref "IC3") (pin "10") (pinfunction "ACT_10") (pintype "bidirectional"))
    )
    (net (code "92") (name "unconnected-(IC3-CTS-Pad18)") (class "Default")
      (node (ref "IC3") (pin "18") (pinfunction "CTS_18") (pintype "bidirectional"))
    )
    (net (code "93") (name "unconnected-(IC3-DCD-Pad24)") (class "Default")
      (node (ref "IC3") (pin "24") (pinfunction "DCD_24") (pintype "bidirectional"))
    )
    (net (code "94") (name "unconnected-(IC3-DSR-Pad22)") (class "Default")
      (node (ref "IC3") (pin "22") (pinfunction "DSR_22") (pintype "bidirectional"))
    )
    (net (code "95") (name "unconnected-(IC3-IO4-Pad16)") (class "Default")
      (node (ref "IC3") (pin "16") (pinfunction "IO4_16") (pintype "bidirectional"))
    )
    (net (code "96") (name "unconnected-(IC3-RI-Pad1)") (class "Default")
      (node (ref "IC3") (pin "1") (pinfunction "RI_1") (pintype "bidirectional"))
    )
    (net (code "97") (name "unconnected-(IC3-RST-Pad9)") (class "Default")
      (node (ref "IC3") (pin "9") (pinfunction "RST_9") (pintype "bidirectional"))
    )
    (net (code "98") (name "unconnected-(IC3-RXS{slash}IO1-Pad13)") (class "Default")
      (node (ref "IC3") (pin "13") (pinfunction "RXS/IO1_13") (pintype "bidirectional"))
    )
    (net (code "99") (name "unconnected-(IC3-SUSPEND#-Pad15)") (class "Default")
      (node (ref "IC3") (pin "15") (pinfunction "SUSPEND#_15") (pintype "bidirectional"))
    )
    (net (code "100") (name "unconnected-(IC3-SUSPEND-Pad17)") (class "Default")
      (node (ref "IC3") (pin "17") (pinfunction "SUSPEND_17") (pintype "bidirectional"))
    )
    (net (code "101") (name "unconnected-(IC3-TNOW{slash}IO2-Pad12)") (class "Default")
      (node (ref "IC3") (pin "12") (pinfunction "TNOW/IO2_12") (pintype "bidirectional"))
    )
    (net (code "102") (name "unconnected-(IC3-TXS{slash}IO0-Pad14)") (class "Default")
      (node (ref "IC3") (pin "14") (pinfunction "TXS/IO0_14") (pintype "bidirectional"))
    )
    (net (code "103") (name "unconnected-(IC3-WAKE{slash}IO3-Pad11)") (class "Default")
      (node (ref "IC3") (pin "11") (pinfunction "WAKE/IO3_11") (pintype "bidirectional"))
    )
    (net (code "104") (name "unconnected-(IC4-NC-Pad4)") (class "Default")
      (node (ref "IC4") (pin "4") (pinfunction "NC_4") (pintype "no_connect"))
    )
    (net (code "105") (name "unconnected-(J4-SBU1-PadA8)") (class "Default")
      (node (ref "J4") (pin "A8") (pinfunction "SBU1_A8") (pintype "passive"))
    )
    (net (code "106") (name "unconnected-(J4-SBU2-PadB8)") (class "Default")
      (node (ref "J4") (pin "B8") (pinfunction "SBU2_B8") (pintype "passive"))
    )
  )
)
